# wagband_schematic_will.net
KiCad netlist of a schematic drawn in EAGLE
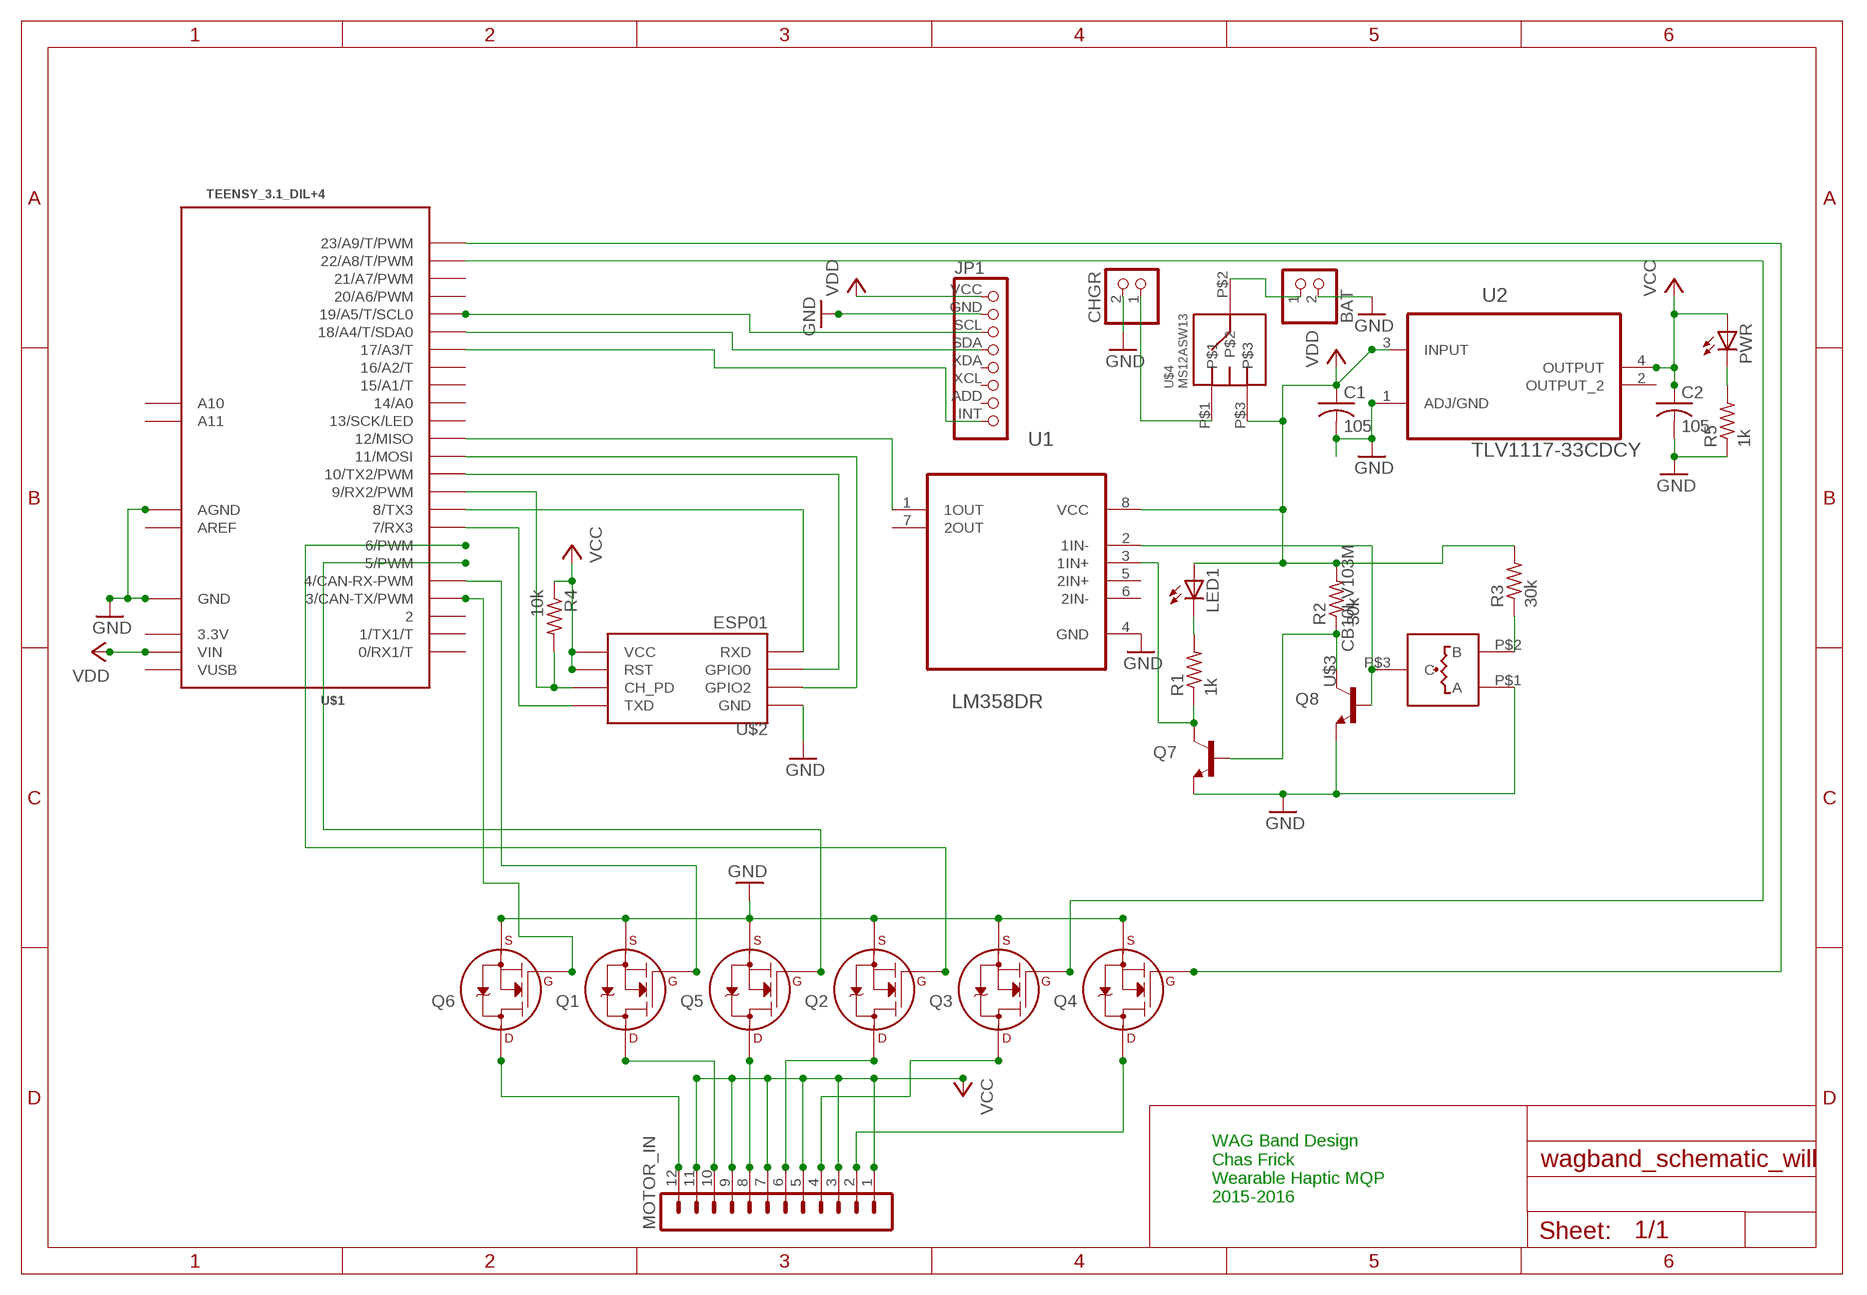
[diagram p0: schematic, sheet 1]

(export (version "E")
  (design (tool "Eeschema 10.0.6"))
  (components
    (comp (ref "BAT")
      (value "JST_2PIN-THM-RA")
      (footprint "eagle-import:JST-PH-2-THM-RA")
      (libsource (lib "eagle-import") (part "JST_2PIN-THM-RA"))
    )
    (comp (ref "C1")
      (value "105")
      (footprint "eagle-import:C0805K")
      (libsource (lib "eagle-import") (part "C-USC0805K"))
    )
    (comp (ref "C2")
      (value "105")
      (footprint "eagle-import:C0805K")
      (libsource (lib "eagle-import") (part "C-USC0805K"))
    )
    (comp (ref "CHGR")
      (value "JST_2PIN-THM-RA")
      (footprint "eagle-import:JST-PH-2-THM-RA")
      (libsource (lib "eagle-import") (part "JST_2PIN-THM-RA"))
    )
    (comp (ref "JP1")
      (value "MPU6050_BREAKOUT")
      (footprint "eagle-import:MPU6050")
      (libsource (lib "eagle-import") (part "MPU6050_BREAKOUT"))
    )
    (comp (ref "LED1")
      (value "LED5MM")
      (footprint "eagle-import:LED5MM")
      (libsource (lib "eagle-import") (part "LED5MM"))
    )
    (comp (ref "MOTOR_IN")
      (value "MA12-1W")
      (footprint "eagle-import:MA12-1W")
      (libsource (lib "eagle-import") (part "MA12-1W"))
    )
    (comp (ref "PWR")
      (value "LED5MM")
      (footprint "eagle-import:LED5MM")
      (libsource (lib "eagle-import") (part "LED5MM"))
    )
    (comp (ref "Q1")
      (value "2N7000_SOT23")
      (footprint "eagle-import:SOT-23")
      (libsource (lib "eagle-import") (part "2N700_SOT230"))
    )
    (comp (ref "Q2")
      (value "2N7000_SOT23")
      (footprint "eagle-import:SOT-23")
      (libsource (lib "eagle-import") (part "2N700_SOT230"))
    )
    (comp (ref "Q3")
      (value "2N7000_SOT23")
      (footprint "eagle-import:SOT-23")
      (libsource (lib "eagle-import") (part "2N700_SOT230"))
    )
    (comp (ref "Q4")
      (value "2N7000_SOT23")
      (footprint "eagle-import:SOT-23")
      (libsource (lib "eagle-import") (part "2N700_SOT230"))
    )
    (comp (ref "Q5")
      (value "2N7000_SOT23")
      (footprint "eagle-import:SOT-23")
      (libsource (lib "eagle-import") (part "2N700_SOT230"))
    )
    (comp (ref "Q6")
      (value "2N7000_SOT23")
      (footprint "eagle-import:SOT-23")
      (libsource (lib "eagle-import") (part "2N700_SOT230"))
    )
    (comp (ref "Q7")
      (value "TRANSISTOR_NPNMMBT3904")
      (footprint "eagle-import:SOT-23")
      (libsource (lib "eagle-import") (part "TRANSISTOR_NPNMMBT3904"))
    )
    (comp (ref "Q8")
      (value "TRANSISTOR_NPNMMBT3904")
      (footprint "eagle-import:SOT-23")
      (libsource (lib "eagle-import") (part "TRANSISTOR_NPNMMBT3904"))
    )
    (comp (ref "R1")
      (value "1k")
      (footprint "eagle-import:R1206")
      (libsource (lib "eagle-import") (part "R-US_R1206"))
    )
    (comp (ref "R2")
      (value "30k")
      (footprint "eagle-import:R1206")
      (libsource (lib "eagle-import") (part "R-US_R1206"))
    )
    (comp (ref "R3")
      (value "30k")
      (footprint "eagle-import:R1206")
      (libsource (lib "eagle-import") (part "R-US_R1206"))
    )
    (comp (ref "R4")
      (value "10k")
      (footprint "eagle-import:R1206")
      (libsource (lib "eagle-import") (part "R-US_R1206"))
    )
    (comp (ref "R5")
      (value "1k")
      (footprint "eagle-import:R1206")
      (libsource (lib "eagle-import") (part "R-US_R1206"))
    )
    (comp (ref "U$1")
      (value "TEENSY_3.1_DIL+4")
      (footprint "eagle-import:TEENSY3-DIL+4")
      (libsource (lib "eagle-import") (part "TEENSY_3.1_DIL+4"))
    )
    (comp (ref "U$2")
      (value "ESP01")
      (footprint "eagle-import:ESP01")
      (libsource (lib "eagle-import") (part "ESP01"))
    )
    (comp (ref "U$3")
      (value "CB10LV103M")
      (footprint "eagle-import:CB10")
      (libsource (lib "eagle-import") (part "CB10LV103M"))
    )
    (comp (ref "U$4")
      (value "MS12ASW13")
      (footprint "eagle-import:SPDT")
      (libsource (lib "eagle-import") (part "MS12ASW13"))
    )
    (comp (ref "U1")
      (value "LM358DR")
      (footprint "eagle-import:SOIC127P600X175-8N")
      (libsource (lib "eagle-import") (part "LM358DR"))
    )
    (comp (ref "U2")
      (value "TLV1117-33CDCY")
      (footprint "eagle-import:SOT230P700X180-4N")
      (libsource (lib "eagle-import") (part "TLV1117-33CDCY"))
    )
  )
  (nets
    (net (code "1") (name "/3.3V") (class "Default")
      (node (ref "U$1") (pin "3.3V") (pinfunction "3.3V_3.3V") (pintype "power_in"))
    )
    (net (code "2") (name "/AREF") (class "Default")
      (node (ref "U$1") (pin "AREF") (pinfunction "AREF_AREF") (pintype "power_in"))
    )
    (net (code "3") (name "/VUSB") (class "Default")
      (node (ref "U$1") (pin "VUSB") (pinfunction "VUSB_VUSB") (pintype "power_in"))
    )
    (net (code "4") (name "GND") (class "Default")
      (node (ref "BAT") (pin "2") (pinfunction "1_2") (pintype "passive"))
      (node (ref "C1") (pin "2") (pinfunction "2_2") (pintype "passive"))
      (node (ref "C2") (pin "2") (pinfunction "2_2") (pintype "passive"))
      (node (ref "CHGR") (pin "2") (pinfunction "1_2") (pintype "passive"))
      (node (ref "JP1") (pin "GND") (pinfunction "GND_GND") (pintype "passive"))
      (node (ref "Q1") (pin "2") (pinfunction "S_2") (pintype "bidirectional"))
      (node (ref "Q2") (pin "2") (pinfunction "S_2") (pintype "bidirectional"))
      (node (ref "Q3") (pin "2") (pinfunction "S_2") (pintype "bidirectional"))
      (node (ref "Q4") (pin "2") (pinfunction "S_2") (pintype "bidirectional"))
      (node (ref "Q5") (pin "2") (pinfunction "S_2") (pintype "bidirectional"))
      (node (ref "Q6") (pin "2") (pinfunction "S_2") (pintype "bidirectional"))
      (node (ref "Q7") (pin "2") (pinfunction "E_2") (pintype "passive"))
      (node (ref "Q8") (pin "2") (pinfunction "E_2") (pintype "passive"))
      (node (ref "R5") (pin "1") (pinfunction "1_1") (pintype "passive"))
      (node (ref "U$1") (pin "AGND") (pinfunction "AGND_AGND") (pintype "power_in"))
      (node (ref "U$1") (pin "GND") (pinfunction "GND_GND") (pintype "power_in"))
      (node (ref "U$2") (pin "GND") (pinfunction "GND_GND") (pintype "bidirectional"))
      (node (ref "U$3") (pin "P$1") (pinfunction "A_P$1") (pintype "bidirectional"))
      (node (ref "U1") (pin "4") (pinfunction "GND_4") (pintype "passive"))
      (node (ref "U2") (pin "1") (pinfunction "ADJ/GND_1") (pintype "input"))
    )
    (net (code "5") (name "Net-(BAT-2)") (class "Default")
      (node (ref "BAT") (pin "1") (pinfunction "2_1") (pintype "passive"))
      (node (ref "U$4") (pin "P$2") (pinfunction "P$2_P$2") (pintype "bidirectional"))
    )
    (net (code "6") (name "Net-(CHGR-2)") (class "Default")
      (node (ref "CHGR") (pin "1") (pinfunction "2_1") (pintype "passive"))
      (node (ref "U$4") (pin "P$1") (pinfunction "P$1_P$1") (pintype "bidirectional"))
    )
    (net (code "7") (name "Net-(LED1-C)") (class "Default")
      (node (ref "LED1") (pin "K") (pinfunction "C_K") (pintype "passive"))
      (node (ref "R1") (pin "2") (pinfunction "2_2") (pintype "passive"))
    )
    (net (code "8") (name "Net-(PWR-C)") (class "Default")
      (node (ref "PWR") (pin "K") (pinfunction "C_K") (pintype "passive"))
      (node (ref "R5") (pin "2") (pinfunction "2_2") (pintype "passive"))
    )
    (net (code "9") (name "Net-(Q1-D)") (class "Default")
      (node (ref "MOTOR_IN") (pin "10") (pinfunction "10_10") (pintype "passive"))
      (node (ref "Q1") (pin "3") (pinfunction "D_3") (pintype "bidirectional"))
    )
    (net (code "10") (name "Net-(Q1-G)") (class "Default")
      (node (ref "Q1") (pin "1") (pinfunction "G_1") (pintype "tri_state"))
      (node (ref "U$1") (pin "4") (pinfunction "4/CAN-RX-PWM_4") (pintype "bidirectional"))
    )
    (net (code "11") (name "Net-(Q2-D)") (class "Default")
      (node (ref "MOTOR_IN") (pin "6") (pinfunction "6_6") (pintype "passive"))
      (node (ref "Q2") (pin "3") (pinfunction "D_3") (pintype "bidirectional"))
    )
    (net (code "12") (name "Net-(Q2-G)") (class "Default")
      (node (ref "Q2") (pin "1") (pinfunction "G_1") (pintype "tri_state"))
      (node (ref "U$1") (pin "6") (pinfunction "6/PWM_6") (pintype "bidirectional"))
    )
    (net (code "13") (name "Net-(Q3-D)") (class "Default")
      (node (ref "MOTOR_IN") (pin "4") (pinfunction "4_4") (pintype "passive"))
      (node (ref "Q3") (pin "3") (pinfunction "D_3") (pintype "bidirectional"))
    )
    (net (code "14") (name "Net-(Q3-G)") (class "Default")
      (node (ref "Q3") (pin "1") (pinfunction "G_1") (pintype "tri_state"))
      (node (ref "U$1") (pin "22/A8") (pinfunction "22/A8/T/PWM_22/A8") (pintype "bidirectional"))
    )
    (net (code "15") (name "Net-(Q4-D)") (class "Default")
      (node (ref "MOTOR_IN") (pin "2") (pinfunction "2_2") (pintype "passive"))
      (node (ref "Q4") (pin "3") (pinfunction "D_3") (pintype "bidirectional"))
    )
    (net (code "16") (name "Net-(Q4-G)") (class "Default")
      (node (ref "Q4") (pin "1") (pinfunction "G_1") (pintype "tri_state"))
      (node (ref "U$1") (pin "23/A9") (pinfunction "23/A9/T/PWM_23/A9") (pintype "bidirectional"))
    )
    (net (code "17") (name "Net-(Q5-D)") (class "Default")
      (node (ref "MOTOR_IN") (pin "8") (pinfunction "8_8") (pintype "passive"))
      (node (ref "Q5") (pin "3") (pinfunction "D_3") (pintype "bidirectional"))
    )
    (net (code "18") (name "Net-(Q5-G)") (class "Default")
      (node (ref "Q5") (pin "1") (pinfunction "G_1") (pintype "tri_state"))
      (node (ref "U$1") (pin "5") (pinfunction "5/PWM_5") (pintype "bidirectional"))
    )
    (net (code "19") (name "Net-(Q6-D)") (class "Default")
      (node (ref "MOTOR_IN") (pin "12") (pinfunction "12_12") (pintype "passive"))
      (node (ref "Q6") (pin "3") (pinfunction "D_3") (pintype "bidirectional"))
    )
    (net (code "20") (name "Net-(Q6-G)") (class "Default")
      (node (ref "Q6") (pin "1") (pinfunction "G_1") (pintype "tri_state"))
      (node (ref "U$1") (pin "3") (pinfunction "3/CAN-TX/PWM_3") (pintype "bidirectional"))
    )
    (net (code "21") (name "Net-(Q7-B)") (class "Default")
      (node (ref "Q7") (pin "1") (pinfunction "B_1") (pintype "passive"))
      (node (ref "Q8") (pin "3") (pinfunction "C_3") (pintype "passive"))
      (node (ref "R2") (pin "1") (pinfunction "1_1") (pintype "passive"))
    )
    (net (code "22") (name "Net-(Q7-C)") (class "Default")
      (node (ref "Q7") (pin "3") (pinfunction "C_3") (pintype "passive"))
      (node (ref "R1") (pin "1") (pinfunction "1_1") (pintype "passive"))
      (node (ref "U1") (pin "3") (pinfunction "1IN+_3") (pintype "input"))
    )
    (net (code "23") (name "Net-(Q8-B)") (class "Default")
      (node (ref "Q8") (pin "1") (pinfunction "B_1") (pintype "passive"))
      (node (ref "U$3") (pin "P$3") (pinfunction "C_P$3") (pintype "bidirectional"))
      (node (ref "U1") (pin "2") (pinfunction "1IN-_2") (pintype "input"))
    )
    (net (code "24") (name "Net-(U$1-7{slash}RX3)") (class "Default")
      (node (ref "U$1") (pin "7") (pinfunction "7/RX3_7") (pintype "bidirectional"))
      (node (ref "U$2") (pin "TX") (pinfunction "TXD_TX") (pintype "bidirectional"))
    )
    (net (code "25") (name "Net-(U$1-8{slash}TX3)") (class "Default")
      (node (ref "U$1") (pin "8") (pinfunction "8/TX3_8") (pintype "bidirectional"))
      (node (ref "U$2") (pin "RX") (pinfunction "RXD_RX") (pintype "bidirectional"))
    )
    (net (code "26") (name "Net-(U$1-9{slash}RX2{slash}PWM)") (class "Default")
      (node (ref "R4") (pin "2") (pinfunction "2_2") (pintype "passive"))
      (node (ref "U$1") (pin "9") (pinfunction "9/RX2/PWM_9") (pintype "bidirectional"))
      (node (ref "U$2") (pin "CH_PD") (pinfunction "CH_PD_CH_PD") (pintype "bidirectional"))
    )
    (net (code "27") (name "Net-(U$1-10{slash}TX2{slash}PWM)") (class "Default")
      (node (ref "U$1") (pin "10") (pinfunction "10/TX2/PWM_10") (pintype "bidirectional"))
      (node (ref "U$2") (pin "GPIO0") (pinfunction "GPIO0_GPIO0") (pintype "bidirectional"))
    )
    (net (code "28") (name "Net-(U$1-11{slash}MOSI)") (class "Default")
      (node (ref "U$1") (pin "11") (pinfunction "11/MOSI_11") (pintype "bidirectional"))
      (node (ref "U$2") (pin "GPIO2") (pinfunction "GPIO2_GPIO2") (pintype "bidirectional"))
    )
    (net (code "29") (name "Net-(U$1-12{slash}MISO)") (class "Default")
      (node (ref "U$1") (pin "12") (pinfunction "12/MISO_12") (pintype "bidirectional"))
      (node (ref "U1") (pin "1") (pinfunction "1OUT_1") (pintype "output"))
    )
    (net (code "30") (name "Net-(U$1-17{slash}A3{slash}T)") (class "Default")
      (node (ref "JP1") (pin "INT") (pinfunction "INT_INT") (pintype "passive"))
      (node (ref "U$1") (pin "17/A3") (pinfunction "17/A3/T_17/A3") (pintype "bidirectional"))
    )
    (net (code "31") (name "Net-(U$1-18{slash}A4{slash}T{slash}SDA0)") (class "Default")
      (node (ref "JP1") (pin "SDA") (pinfunction "SDA_SDA") (pintype "passive"))
      (node (ref "U$1") (pin "18/A4") (pinfunction "18/A4/T/SDA0_18/A4") (pintype "bidirectional"))
    )
    (net (code "32") (name "Net-(U$1-19{slash}A5{slash}T{slash}SCL0)") (class "Default")
      (node (ref "JP1") (pin "SCL") (pinfunction "SCL_SCL") (pintype "passive"))
      (node (ref "U$1") (pin "19/A5") (pinfunction "19/A5/T/SCL0_19/A5") (pintype "bidirectional"))
    )
    (net (code "33") (name "Net-(U$3-B)") (class "Default")
      (node (ref "R3") (pin "1") (pinfunction "1_1") (pintype "passive"))
      (node (ref "U$3") (pin "P$2") (pinfunction "B_P$2") (pintype "bidirectional"))
    )
    (net (code "34") (name "VCC") (class "Default")
      (node (ref "C1") (pin "1") (pinfunction "1_1") (pintype "passive"))
      (node (ref "C2") (pin "1") (pinfunction "1_1") (pintype "passive"))
      (node (ref "JP1") (pin "VCC") (pinfunction "VCC_VCC") (pintype "passive"))
      (node (ref "LED1") (pin "A") (pinfunction "A_A") (pintype "passive"))
      (node (ref "MOTOR_IN") (pin "1") (pinfunction "1_1") (pintype "passive"))
      (node (ref "MOTOR_IN") (pin "11") (pinfunction "11_11") (pintype "passive"))
      (node (ref "MOTOR_IN") (pin "3") (pinfunction "3_3") (pintype "passive"))
      (node (ref "MOTOR_IN") (pin "5") (pinfunction "5_5") (pintype "passive"))
      (node (ref "MOTOR_IN") (pin "7") (pinfunction "7_7") (pintype "passive"))
      (node (ref "MOTOR_IN") (pin "9") (pinfunction "9_9") (pintype "passive"))
      (node (ref "PWR") (pin "A") (pinfunction "A_A") (pintype "passive"))
      (node (ref "R2") (pin "2") (pinfunction "2_2") (pintype "passive"))
      (node (ref "R3") (pin "2") (pinfunction "2_2") (pintype "passive"))
      (node (ref "R4") (pin "1") (pinfunction "1_1") (pintype "passive"))
      (node (ref "U$1") (pin "VIN") (pinfunction "VIN_VIN") (pintype "power_in"))
      (node (ref "U$2") (pin "RST") (pinfunction "RST_RST") (pintype "bidirectional"))
      (node (ref "U$2") (pin "VCC") (pinfunction "VCC_VCC") (pintype "bidirectional"))
      (node (ref "U$4") (pin "P$3") (pinfunction "P$3_P$3") (pintype "bidirectional"))
      (node (ref "U1") (pin "8") (pinfunction "VCC_8") (pintype "power_in"))
      (node (ref "U2") (pin "3") (pinfunction "INPUT_3") (pintype "input"))
      (node (ref "U2") (pin "4") (pinfunction "OUTPUT_4") (pintype "output"))
    )
    (net (code "35") (name "unconnected-(JP1-PadADD)") (class "Default")
      (node (ref "JP1") (pin "ADD") (pinfunction "ADD_ADD") (pintype "passive"))
    )
    (net (code "36") (name "unconnected-(JP1-PadXCL)") (class "Default")
      (node (ref "JP1") (pin "XCL") (pinfunction "XCL_XCL") (pintype "passive"))
    )
    (net (code "37") (name "unconnected-(JP1-PadXDA)") (class "Default")
      (node (ref "JP1") (pin "XDA") (pinfunction "XDA_XDA") (pintype "passive"))
    )
    (net (code "38") (name "unconnected-(U$1-0{slash}RX1{slash}T-Pad0)") (class "Default")
      (node (ref "U$1") (pin "0") (pinfunction "0/RX1/T_0") (pintype "bidirectional"))
    )
    (net (code "39") (name "unconnected-(U$1-1{slash}TX1{slash}T-Pad1)") (class "Default")
      (node (ref "U$1") (pin "1") (pinfunction "1/TX1/T_1") (pintype "bidirectional"))
    )
    (net (code "40") (name "unconnected-(U$1-13{slash}SCK{slash}LED-Pad13)") (class "Default")
      (node (ref "U$1") (pin "13") (pinfunction "13/SCK/LED_13") (pintype "bidirectional"))
    )
    (net (code "41") (name "unconnected-(U$1-15{slash}A1{slash}T-Pad15{slash}A1)") (class "Default")
      (node (ref "U$1") (pin "15/A1") (pinfunction "15/A1/T_15/A1") (pintype "bidirectional"))
    )
    (net (code "42") (name "unconnected-(U$1-16{slash}A2{slash}T-Pad16{slash}A2)") (class "Default")
      (node (ref "U$1") (pin "16/A2") (pinfunction "16/A2/T_16/A2") (pintype "bidirectional"))
    )
    (net (code "43") (name "unconnected-(U$1-20{slash}A6{slash}PWM-Pad20{slash}A6)") (class "Default")
      (node (ref "U$1") (pin "20/A6") (pinfunction "20/A6/PWM_20/A6") (pintype "bidirectional"))
    )
    (net (code "44") (name "unconnected-(U$1-21{slash}A7{slash}PWM-Pad21{slash}A7)") (class "Default")
      (node (ref "U$1") (pin "21/A7") (pinfunction "21/A7/PWM_21/A7") (pintype "bidirectional"))
    )
    (net (code "45") (name "unconnected-(U$1-Pad2)") (class "Default")
      (node (ref "U$1") (pin "2") (pinfunction "2_2") (pintype "bidirectional"))
    )
    (net (code "46") (name "unconnected-(U$1-Pad14{slash}A0)") (class "Default")
      (node (ref "U$1") (pin "14/A0") (pinfunction "14/A0_14/A0") (pintype "bidirectional"))
    )
    (net (code "47") (name "unconnected-(U$1-PadA10)") (class "Default")
      (node (ref "U$1") (pin "A10") (pinfunction "A10_A10") (pintype "bidirectional"))
    )
    (net (code "48") (name "unconnected-(U$1-PadA11)") (class "Default")
      (node (ref "U$1") (pin "A11") (pinfunction "A11_A11") (pintype "bidirectional"))
    )
    (net (code "49") (name "unconnected-(U1-2IN+-Pad5)") (class "Default")
      (node (ref "U1") (pin "5") (pinfunction "2IN+_5") (pintype "input"))
    )
    (net (code "50") (name "unconnected-(U1-2IN--Pad6)") (class "Default")
      (node (ref "U1") (pin "6") (pinfunction "2IN-_6") (pintype "input"))
    )
    (net (code "51") (name "unconnected-(U1-2OUT-Pad7)") (class "Default")
      (node (ref "U1") (pin "7") (pinfunction "2OUT_7") (pintype "output"))
    )
    (net (code "52") (name "unconnected-(U2-OUTPUT_2-Pad2)") (class "Default")
      (node (ref "U2") (pin "2") (pinfunction "OUTPUT_2_2") (pintype "output"))
    )
  )
)
